# dus-lmt_breakout.net
KiCad netlist of a schematic drawn in EAGLE
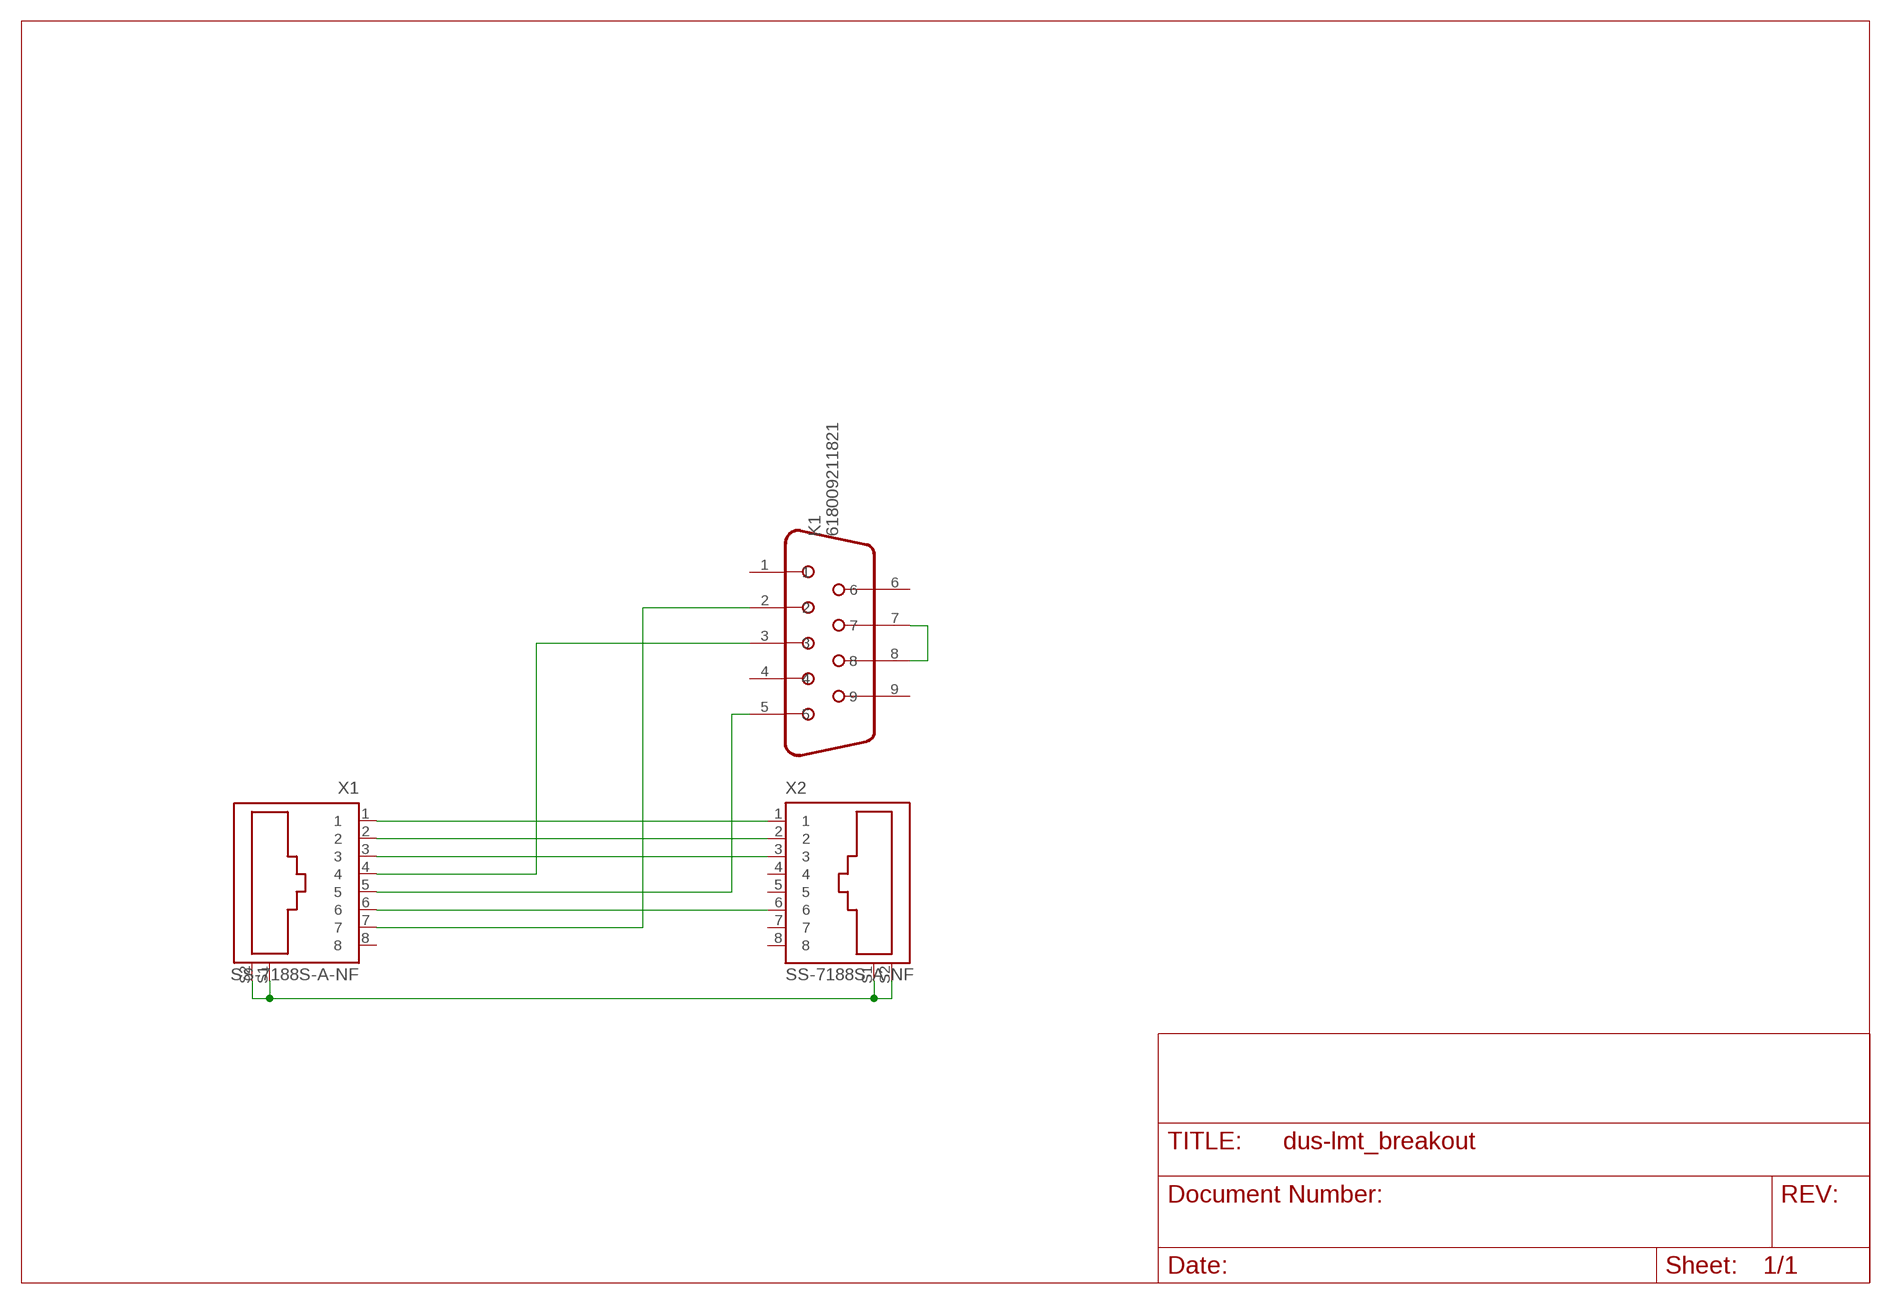
[diagram p0: schematic, sheet 1]

(export (version "E")
  (design (tool "Eeschema 10.0.6"))
  (components
    (comp (ref "K1")
      (value "618009211821")
      (footprint "eagle-import:618009211821")
      (libsource (lib "eagle-import") (part "618009211821"))
    )
    (comp (ref "X1")
      (value "SS-7188S-A-NF")
      (footprint "eagle-import:SS-7188S-A-NF")
      (fields (field (name "MANUFACTURER") "Bel Stewart"))
      (libsource (lib "eagle-import") (part "SS-7188S-A-NF"))
    )
    (comp (ref "X2")
      (value "SS-7188S-A-NF")
      (footprint "eagle-import:SS-7188S-A-NF")
      (fields (field (name "MANUFACTURER") "Bel Stewart"))
      (libsource (lib "eagle-import") (part "SS-7188S-A-NF"))
    )
  )
  (nets
    (net (code "1") (name "Net-(K1-Pad2)") (class "Default")
      (node (ref "K1") (pin "2") (pinfunction "2_2") (pintype "bidirectional"))
      (node (ref "X1") (pin "7") (pinfunction "7_7") (pintype "passive"))
    )
    (net (code "2") (name "Net-(K1-Pad3)") (class "Default")
      (node (ref "K1") (pin "3") (pinfunction "3_3") (pintype "bidirectional"))
      (node (ref "X1") (pin "4") (pinfunction "4_4") (pintype "passive"))
    )
    (net (code "3") (name "Net-(K1-Pad5)") (class "Default")
      (node (ref "K1") (pin "5") (pinfunction "5_5") (pintype "bidirectional"))
      (node (ref "X1") (pin "5") (pinfunction "5_5") (pintype "passive"))
    )
    (net (code "4") (name "Net-(K1-Pad7)") (class "Default")
      (node (ref "K1") (pin "7") (pinfunction "7_7") (pintype "bidirectional"))
      (node (ref "K1") (pin "8") (pinfunction "8_8") (pintype "bidirectional"))
    )
    (net (code "5") (name "Net-(X1-Pad1)") (class "Default")
      (node (ref "X1") (pin "1") (pinfunction "1_1") (pintype "passive"))
      (node (ref "X2") (pin "1") (pinfunction "1_1") (pintype "passive"))
    )
    (net (code "6") (name "Net-(X1-Pad2)") (class "Default")
      (node (ref "X1") (pin "2") (pinfunction "2_2") (pintype "passive"))
      (node (ref "X2") (pin "2") (pinfunction "2_2") (pintype "passive"))
    )
    (net (code "7") (name "Net-(X1-Pad3)") (class "Default")
      (node (ref "X1") (pin "3") (pinfunction "3_3") (pintype "passive"))
      (node (ref "X2") (pin "3") (pinfunction "3_3") (pintype "passive"))
    )
    (net (code "8") (name "Net-(X1-Pad6)") (class "Default")
      (node (ref "X1") (pin "6") (pinfunction "6_6") (pintype "passive"))
      (node (ref "X2") (pin "6") (pinfunction "6_6") (pintype "passive"))
    )
    (net (code "9") (name "Net-(X1-PadS1)") (class "Default")
      (node (ref "X1") (pin "S1") (pinfunction "S1_S1") (pintype "passive"))
      (node (ref "X1") (pin "S2") (pinfunction "S2_S2") (pintype "passive"))
      (node (ref "X2") (pin "S1") (pinfunction "S1_S1") (pintype "passive"))
      (node (ref "X2") (pin "S2") (pinfunction "S2_S2") (pintype "passive"))
    )
    (net (code "10") (name "unconnected-(K1-Pad1)") (class "Default")
      (node (ref "K1") (pin "1") (pinfunction "1_1") (pintype "bidirectional"))
    )
    (net (code "11") (name "unconnected-(K1-Pad4)") (class "Default")
      (node (ref "K1") (pin "4") (pinfunction "4_4") (pintype "bidirectional"))
    )
    (net (code "12") (name "unconnected-(K1-Pad6)") (class "Default")
      (node (ref "K1") (pin "6") (pinfunction "6_6") (pintype "bidirectional"))
    )
    (net (code "13") (name "unconnected-(K1-Pad9)") (class "Default")
      (node (ref "K1") (pin "9") (pinfunction "9_9") (pintype "bidirectional"))
    )
    (net (code "14") (name "unconnected-(X1-Pad8)") (class "Default")
      (node (ref "X1") (pin "8") (pinfunction "8_8") (pintype "passive"))
    )
    (net (code "15") (name "unconnected-(X2-Pad4)") (class "Default")
      (node (ref "X2") (pin "4") (pinfunction "4_4") (pintype "passive"))
    )
    (net (code "16") (name "unconnected-(X2-Pad5)") (class "Default")
      (node (ref "X2") (pin "5") (pinfunction "5_5") (pintype "passive"))
    )
    (net (code "17") (name "unconnected-(X2-Pad7)") (class "Default")
      (node (ref "X2") (pin "7") (pinfunction "7_7") (pintype "passive"))
    )
    (net (code "18") (name "unconnected-(X2-Pad8)") (class "Default")
      (node (ref "X2") (pin "8") (pinfunction "8_8") (pintype "passive"))
    )
  )
)
